# Sheet_1_2026-05-26.net
KiCad netlist of a schematic drawn in Altium Designer
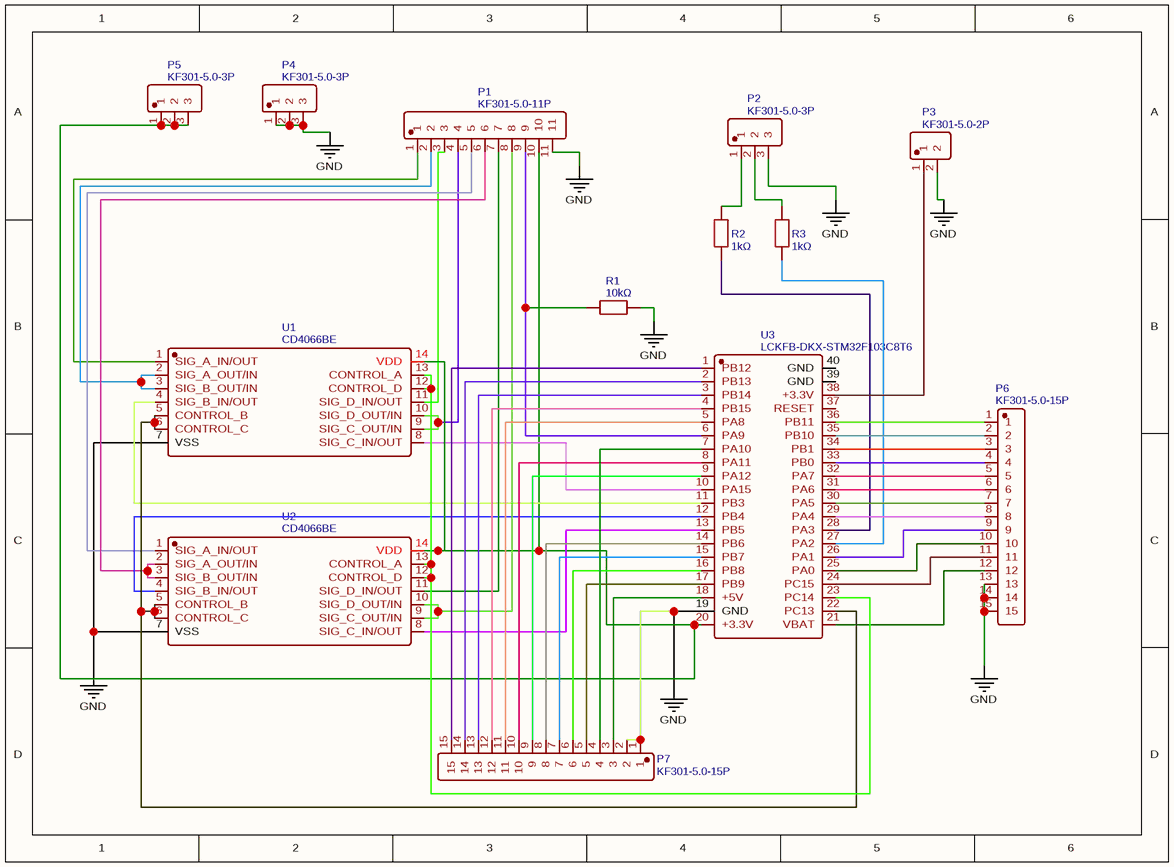
[diagram p0: Sheet_1_2026-05-26.schdoc]

(export (version "E")
  (design (tool "Eeschema 10.0.6"))
  (components
    (comp (ref "P1")
      (value "KF301-5.0-11P")
      (fields (field (name "CONTRIBUTOR") "LCSC"))
      (libsource (lib "altium-import") (part "root_1_KF301-5.0-11P_"))
    )
    (comp (ref "P2")
      (value "KF301-5.0-3P")
      (fields (field (name "MANUFACTURER") "KEFA(科发)") (field (name "CONTRIBUTOR") "LCSC"))
      (libsource (lib "altium-import") (part "root_1_KF301-5.0-3P_"))
    )
    (comp (ref "P3")
      (value "KF301-5.0-2P")
      (fields (field (name "MANUFACTURER") "KEFA(科发)") (field (name "CONTRIBUTOR") "LCSC"))
      (libsource (lib "altium-import") (part "root_1_KF301-5.0-2P_"))
    )
    (comp (ref "P4")
      (value "KF301-5.0-3P")
      (fields (field (name "MANUFACTURER") "KEFA(科发)") (field (name "CONTRIBUTOR") "LCSC"))
      (libsource (lib "altium-import") (part "root_1_KF301-5.0-3P_"))
    )
    (comp (ref "P5")
      (value "KF301-5.0-3P")
      (fields (field (name "MANUFACTURER") "KEFA(科发)") (field (name "CONTRIBUTOR") "LCSC"))
      (libsource (lib "altium-import") (part "root_1_KF301-5.0-3P_"))
    )
    (comp (ref "P6")
      (value "KF301-5.0-15P")
      (fields (field (name "CONTRIBUTOR") "LCSC"))
      (libsource (lib "altium-import") (part "root_0_KF301-5.0-15P_"))
    )
    (comp (ref "P7")
      (value "KF301-5.0-15P")
      (fields (field (name "CONTRIBUTOR") "LCSC"))
      (libsource (lib "altium-import") (part "root_3_KF301-5.0-15P_"))
    )
    (comp (ref "R1")
      (value "10kΩ")
      (fields
        (field (name "MANUFACTURER") "Tyohm(幸亚电阻)")
        (field (name "MANUFACTURER PART") "RN1/4W10KFT/BA1")
        (field (name "CONTRIBUTOR") "LCSC")
      )
      (libsource (lib "altium-import") (part "root_0_10kΩ_"))
    )
    (comp (ref "R2")
      (value "1kΩ")
      (fields
        (field (name "MANUFACTURER") "Tyohm(幸亚电阻)")
        (field (name "MANUFACTURER PART") "RN1/4W10KFT/BA1")
        (field (name "CONTRIBUTOR") "LCSC")
      )
      (libsource (lib "altium-import") (part "root_3_1kΩ_"))
    )
    (comp (ref "R3")
      (value "1kΩ")
      (fields
        (field (name "MANUFACTURER") "Tyohm(幸亚电阻)")
        (field (name "MANUFACTURER PART") "RN1/4W10KFT/BA1")
        (field (name "CONTRIBUTOR") "LCSC")
      )
      (libsource (lib "altium-import") (part "root_3_1kΩ_"))
    )
    (comp (ref "U1")
      (value "CD4066BE")
      (fields (field (name "MANUFACTURER") "TI(德州仪器)"))
      (libsource (lib "altium-import") (part "root_0_CD4066BE_"))
    )
    (comp (ref "U2")
      (value "CD4066BE")
      (fields (field (name "MANUFACTURER") "TI(德州仪器)"))
      (libsource (lib "altium-import") (part "root_0_CD4066BE_"))
    )
    (comp (ref "U3")
      (value "LCKFB-DKX-STM32F103C8T6")
      (fields (field (name "MANUFACTURER") "立创开发板") (field (name "CONTRIBUTOR") "lcsc"))
      (libsource (lib "altium-import") (part "root_0_LCKFB-DKX-STM32F103C8T6_"))
    )
  )
  (nets
    (net (code "1") (name "GND") (class "Default")
      (node (ref "P1") (pin "11") (pinfunction "11_11") (pintype "passive"))
      (node (ref "P2") (pin "3") (pinfunction "3_3") (pintype "passive"))
      (node (ref "P3") (pin "2") (pinfunction "2_2") (pintype "passive"))
      (node (ref "P4") (pin "1") (pinfunction "1_1") (pintype "passive"))
      (node (ref "P4") (pin "2") (pinfunction "2_2") (pintype "passive"))
      (node (ref "P4") (pin "3") (pinfunction "3_3") (pintype "passive"))
      (node (ref "P6") (pin "13") (pinfunction "13_13") (pintype "passive"))
      (node (ref "P6") (pin "14") (pinfunction "14_14") (pintype "passive"))
      (node (ref "P6") (pin "15") (pinfunction "15_15") (pintype "passive"))
      (node (ref "P7") (pin "1") (pinfunction "1_1") (pintype "passive"))
      (node (ref "P7") (pin "2") (pinfunction "2_2") (pintype "passive"))
      (node (ref "R1") (pin "2") (pinfunction "2_2") (pintype "passive"))
      (node (ref "U1") (pin "7") (pinfunction "VSS_7") (pintype "passive"))
      (node (ref "U2") (pin "7") (pinfunction "VSS_7") (pintype "passive"))
      (node (ref "U3") (pin "19") (pinfunction "GND_19") (pintype "passive"))
    )
    (net (code "2") (name "Net-(P2-Pad1)") (class "Default")
      (node (ref "P2") (pin "1") (pinfunction "1_1") (pintype "passive"))
      (node (ref "R2") (pin "1") (pinfunction "1_1") (pintype "passive"))
    )
    (net (code "3") (name "Net-(P2-Pad2)") (class "Default")
      (node (ref "P2") (pin "2") (pinfunction "2_2") (pintype "passive"))
      (node (ref "R3") (pin "1") (pinfunction "1_1") (pintype "passive"))
    )
    (net (code "4") (name "Net-(P3-Pad1)") (class "Default")
      (node (ref "P3") (pin "1") (pinfunction "1_1") (pintype "passive"))
      (node (ref "U3") (pin "38") (pinfunction "+3.3V_38") (pintype "passive"))
    )
    (net (code "5") (name "Net-(U1-CONTROL_A)") (class "Default")
      (node (ref "U1") (pin "12") (pinfunction "CONTROL_D_12") (pintype "passive"))
      (node (ref "U1") (pin "13") (pinfunction "CONTROL_A_13") (pintype "passive"))
      (node (ref "U2") (pin "12") (pinfunction "CONTROL_D_12") (pintype "passive"))
      (node (ref "U2") (pin "13") (pinfunction "CONTROL_A_13") (pintype "passive"))
      (node (ref "U3") (pin "23") (pinfunction "PC14_23") (pintype "passive"))
    )
    (net (code "6") (name "Net-(U1-CONTROL_B)") (class "Default")
      (node (ref "U1") (pin "5") (pinfunction "CONTROL_B_5") (pintype "passive"))
      (node (ref "U1") (pin "6") (pinfunction "CONTROL_C_6") (pintype "passive"))
      (node (ref "U2") (pin "5") (pinfunction "CONTROL_B_5") (pintype "passive"))
      (node (ref "U2") (pin "6") (pinfunction "CONTROL_C_6") (pintype "passive"))
      (node (ref "U3") (pin "22") (pinfunction "PC13_22") (pintype "passive"))
    )
    (net (code "7") (name "Net-(U1-SIG_A_IN{slash}OUT)") (class "Default")
      (node (ref "P1") (pin "1") (pinfunction "1_1") (pintype "passive"))
      (node (ref "U1") (pin "1") (pinfunction "SIG_A_IN/OUT_1") (pintype "passive"))
    )
    (net (code "8") (name "Net-(U1-SIG_A_OUT{slash}IN)") (class "Default")
      (node (ref "P1") (pin "2") (pinfunction "2_2") (pintype "passive"))
      (node (ref "U1") (pin "2") (pinfunction "SIG_A_OUT/IN_2") (pintype "passive"))
      (node (ref "U1") (pin "3") (pinfunction "SIG_B_OUT/IN_3") (pintype "passive"))
    )
    (net (code "9") (name "Net-(U1-SIG_B_IN{slash}OUT)") (class "Default")
      (node (ref "U1") (pin "4") (pinfunction "SIG_B_IN/OUT_4") (pintype "passive"))
      (node (ref "U3") (pin "11") (pinfunction "PB3_11") (pintype "passive"))
    )
    (net (code "10") (name "Net-(U1-SIG_C_IN{slash}OUT)") (class "Default")
      (node (ref "U1") (pin "8") (pinfunction "SIG_C_IN/OUT_8") (pintype "passive"))
      (node (ref "U3") (pin "10") (pinfunction "PA15_10") (pintype "passive"))
    )
    (net (code "11") (name "Net-(U1-SIG_C_OUT{slash}IN)") (class "Default")
      (node (ref "P1") (pin "4") (pinfunction "4_4") (pintype "passive"))
      (node (ref "U1") (pin "10") (pinfunction "SIG_D_OUT/IN_10") (pintype "passive"))
      (node (ref "U1") (pin "9") (pinfunction "SIG_C_OUT/IN_9") (pintype "passive"))
    )
    (net (code "12") (name "Net-(U1-SIG_D_IN{slash}OUT)") (class "Default")
      (node (ref "P1") (pin "3") (pinfunction "3_3") (pintype "passive"))
      (node (ref "U1") (pin "11") (pinfunction "SIG_D_IN/OUT_11") (pintype "passive"))
    )
    (net (code "13") (name "Net-(U1-VDD)") (class "Default")
      (node (ref "P1") (pin "10") (pinfunction "10_10") (pintype "passive"))
      (node (ref "P5") (pin "1") (pinfunction "1_1") (pintype "passive"))
      (node (ref "P5") (pin "2") (pinfunction "2_2") (pintype "passive"))
      (node (ref "P5") (pin "3") (pinfunction "3_3") (pintype "passive"))
      (node (ref "U1") (pin "14") (pinfunction "VDD_14") (pintype "passive"))
      (node (ref "U2") (pin "14") (pinfunction "VDD_14") (pintype "passive"))
      (node (ref "U3") (pin "20") (pinfunction "+3.3V_20") (pintype "passive"))
    )
    (net (code "14") (name "Net-(U2-SIG_A_IN{slash}OUT)") (class "Default")
      (node (ref "P1") (pin "5") (pinfunction "5_5") (pintype "passive"))
      (node (ref "U2") (pin "1") (pinfunction "SIG_A_IN/OUT_1") (pintype "passive"))
    )
    (net (code "15") (name "Net-(U2-SIG_A_OUT{slash}IN)") (class "Default")
      (node (ref "P1") (pin "6") (pinfunction "6_6") (pintype "passive"))
      (node (ref "U2") (pin "2") (pinfunction "SIG_A_OUT/IN_2") (pintype "passive"))
      (node (ref "U2") (pin "3") (pinfunction "SIG_B_OUT/IN_3") (pintype "passive"))
    )
    (net (code "16") (name "Net-(U2-SIG_B_IN{slash}OUT)") (class "Default")
      (node (ref "U2") (pin "4") (pinfunction "SIG_B_IN/OUT_4") (pintype "passive"))
      (node (ref "U3") (pin "12") (pinfunction "PB4_12") (pintype "passive"))
    )
    (net (code "17") (name "Net-(U2-SIG_C_IN{slash}OUT)") (class "Default")
      (node (ref "U2") (pin "8") (pinfunction "SIG_C_IN/OUT_8") (pintype "passive"))
      (node (ref "U3") (pin "13") (pinfunction "PB5_13") (pintype "passive"))
    )
    (net (code "18") (name "Net-(U2-SIG_C_OUT{slash}IN)") (class "Default")
      (node (ref "P1") (pin "8") (pinfunction "8_8") (pintype "passive"))
      (node (ref "U2") (pin "10") (pinfunction "SIG_D_OUT/IN_10") (pintype "passive"))
      (node (ref "U2") (pin "9") (pinfunction "SIG_C_OUT/IN_9") (pintype "passive"))
    )
    (net (code "19") (name "Net-(U2-SIG_D_IN{slash}OUT)") (class "Default")
      (node (ref "P1") (pin "7") (pinfunction "7_7") (pintype "passive"))
      (node (ref "U2") (pin "11") (pinfunction "SIG_D_IN/OUT_11") (pintype "passive"))
    )
    (net (code "20") (name "Net-(U3-+5V)") (class "Default")
      (node (ref "P7") (pin "3") (pinfunction "3_3") (pintype "passive"))
      (node (ref "U3") (pin "18") (pinfunction "+5V_18") (pintype "passive"))
    )
    (net (code "21") (name "Net-(U3-PA0)") (class "Default")
      (node (ref "P6") (pin "10") (pinfunction "10_10") (pintype "passive"))
      (node (ref "U3") (pin "25") (pinfunction "PA0_25") (pintype "passive"))
    )
    (net (code "22") (name "Net-(U3-PA1)") (class "Default")
      (node (ref "P6") (pin "9") (pinfunction "9_9") (pintype "passive"))
      (node (ref "U3") (pin "26") (pinfunction "PA1_26") (pintype "passive"))
    )
    (net (code "23") (name "Net-(U3-PA2)") (class "Default")
      (node (ref "R3") (pin "2") (pinfunction "2_2") (pintype "passive"))
      (node (ref "U3") (pin "27") (pinfunction "PA2_27") (pintype "passive"))
    )
    (net (code "24") (name "Net-(U3-PA3)") (class "Default")
      (node (ref "R2") (pin "2") (pinfunction "2_2") (pintype "passive"))
      (node (ref "U3") (pin "28") (pinfunction "PA3_28") (pintype "passive"))
    )
    (net (code "25") (name "Net-(U3-PA4)") (class "Default")
      (node (ref "P6") (pin "8") (pinfunction "8_8") (pintype "passive"))
      (node (ref "U3") (pin "29") (pinfunction "PA4_29") (pintype "passive"))
    )
    (net (code "26") (name "Net-(U3-PA5)") (class "Default")
      (node (ref "P6") (pin "7") (pinfunction "7_7") (pintype "passive"))
      (node (ref "U3") (pin "30") (pinfunction "PA5_30") (pintype "passive"))
    )
    (net (code "27") (name "Net-(U3-PA6)") (class "Default")
      (node (ref "P6") (pin "6") (pinfunction "6_6") (pintype "passive"))
      (node (ref "U3") (pin "31") (pinfunction "PA6_31") (pintype "passive"))
    )
    (net (code "28") (name "Net-(U3-PA7)") (class "Default")
      (node (ref "P6") (pin "5") (pinfunction "5_5") (pintype "passive"))
      (node (ref "U3") (pin "32") (pinfunction "PA7_32") (pintype "passive"))
    )
    (net (code "29") (name "Net-(U3-PA8)") (class "Default")
      (node (ref "P7") (pin "11") (pinfunction "11_11") (pintype "passive"))
      (node (ref "U3") (pin "5") (pinfunction "PA8_5") (pintype "passive"))
    )
    (net (code "30") (name "Net-(U3-PA9)") (class "Default")
      (node (ref "P1") (pin "9") (pinfunction "9_9") (pintype "passive"))
      (node (ref "R1") (pin "1") (pinfunction "1_1") (pintype "passive"))
      (node (ref "U3") (pin "6") (pinfunction "PA9_6") (pintype "passive"))
    )
    (net (code "31") (name "Net-(U3-PA10)") (class "Default")
      (node (ref "P7") (pin "4") (pinfunction "4_4") (pintype "passive"))
      (node (ref "U3") (pin "7") (pinfunction "PA10_7") (pintype "passive"))
    )
    (net (code "32") (name "Net-(U3-PA11)") (class "Default")
      (node (ref "P7") (pin "10") (pinfunction "10_10") (pintype "passive"))
      (node (ref "U3") (pin "8") (pinfunction "PA11_8") (pintype "passive"))
    )
    (net (code "33") (name "Net-(U3-PA12)") (class "Default")
      (node (ref "P7") (pin "9") (pinfunction "9_9") (pintype "passive"))
      (node (ref "U3") (pin "9") (pinfunction "PA12_9") (pintype "passive"))
    )
    (net (code "34") (name "Net-(U3-PB0)") (class "Default")
      (node (ref "P6") (pin "4") (pinfunction "4_4") (pintype "passive"))
      (node (ref "U3") (pin "33") (pinfunction "PB0_33") (pintype "passive"))
    )
    (net (code "35") (name "Net-(U3-PB1)") (class "Default")
      (node (ref "P6") (pin "3") (pinfunction "3_3") (pintype "passive"))
      (node (ref "U3") (pin "34") (pinfunction "PB1_34") (pintype "passive"))
    )
    (net (code "36") (name "Net-(U3-PB6)") (class "Default")
      (node (ref "P7") (pin "8") (pinfunction "8_8") (pintype "passive"))
      (node (ref "U3") (pin "14") (pinfunction "PB6_14") (pintype "passive"))
    )
    (net (code "37") (name "Net-(U3-PB7)") (class "Default")
      (node (ref "P7") (pin "7") (pinfunction "7_7") (pintype "passive"))
      (node (ref "U3") (pin "15") (pinfunction "PB7_15") (pintype "passive"))
    )
    (net (code "38") (name "Net-(U3-PB8)") (class "Default")
      (node (ref "P7") (pin "6") (pinfunction "6_6") (pintype "passive"))
      (node (ref "U3") (pin "16") (pinfunction "PB8_16") (pintype "passive"))
    )
    (net (code "39") (name "Net-(U3-PB9)") (class "Default")
      (node (ref "P7") (pin "5") (pinfunction "5_5") (pintype "passive"))
      (node (ref "U3") (pin "17") (pinfunction "PB9_17") (pintype "passive"))
    )
    (net (code "40") (name "Net-(U3-PB10)") (class "Default")
      (node (ref "P6") (pin "2") (pinfunction "2_2") (pintype "passive"))
      (node (ref "U3") (pin "35") (pinfunction "PB10_35") (pintype "passive"))
    )
    (net (code "41") (name "Net-(U3-PB11)") (class "Default")
      (node (ref "P6") (pin "1") (pinfunction "1_1") (pintype "passive"))
      (node (ref "U3") (pin "36") (pinfunction "PB11_36") (pintype "passive"))
    )
    (net (code "42") (name "Net-(U3-PB12)") (class "Default")
      (node (ref "P7") (pin "15") (pinfunction "15_15") (pintype "passive"))
      (node (ref "U3") (pin "1") (pinfunction "PB12_1") (pintype "passive"))
    )
    (net (code "43") (name "Net-(U3-PB13)") (class "Default")
      (node (ref "P7") (pin "14") (pinfunction "14_14") (pintype "passive"))
      (node (ref "U3") (pin "2") (pinfunction "PB13_2") (pintype "passive"))
    )
    (net (code "44") (name "Net-(U3-PB14)") (class "Default")
      (node (ref "P7") (pin "13") (pinfunction "13_13") (pintype "passive"))
      (node (ref "U3") (pin "3") (pinfunction "PB14_3") (pintype "passive"))
    )
    (net (code "45") (name "Net-(U3-PB15)") (class "Default")
      (node (ref "P7") (pin "12") (pinfunction "12_12") (pintype "passive"))
      (node (ref "U3") (pin "4") (pinfunction "PB15_4") (pintype "passive"))
    )
    (net (code "46") (name "Net-(U3-PC15)") (class "Default")
      (node (ref "P6") (pin "11") (pinfunction "11_11") (pintype "passive"))
      (node (ref "U3") (pin "24") (pinfunction "PC15_24") (pintype "passive"))
    )
    (net (code "47") (name "Net-(U3-VBAT)") (class "Default")
      (node (ref "P6") (pin "12") (pinfunction "12_12") (pintype "passive"))
      (node (ref "U3") (pin "21") (pinfunction "VBAT_21") (pintype "passive"))
    )
    (net (code "48") (name "unconnected-(U3-GND-Pad39)") (class "Default")
      (node (ref "U3") (pin "39") (pinfunction "GND_39") (pintype "passive"))
    )
    (net (code "49") (name "unconnected-(U3-GND-Pad40)") (class "Default")
      (node (ref "U3") (pin "40") (pinfunction "GND_40") (pintype "passive"))
    )
    (net (code "50") (name "unconnected-(U3-RESET-Pad37)") (class "Default")
      (node (ref "U3") (pin "37") (pinfunction "RESET_37") (pintype "passive"))
    )
  )
)
